# Ensemble_ProtoBoard.net
KiCad netlist of a schematic drawn in EAGLE
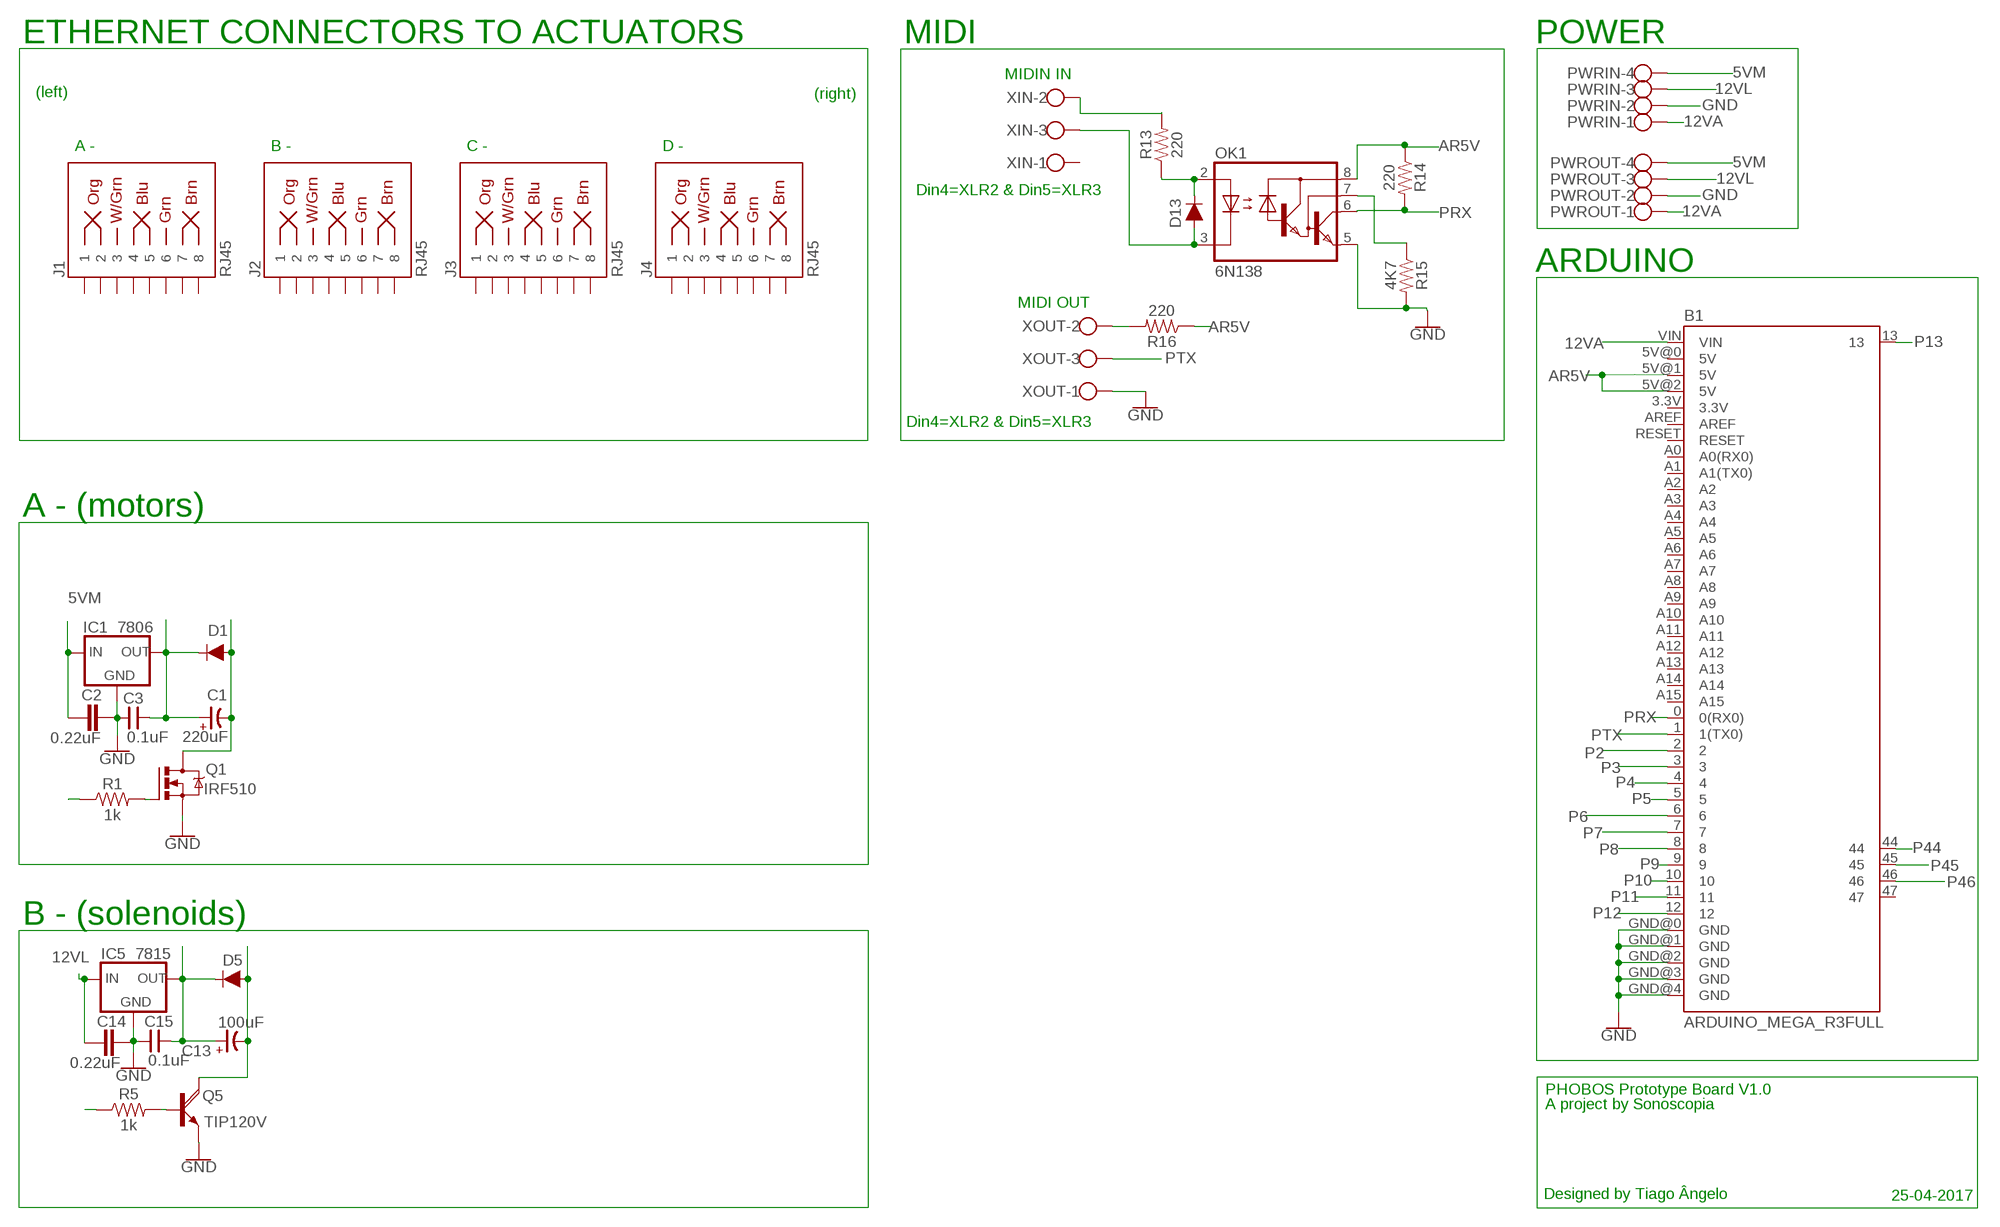
[diagram p0: schematic, sheet 1]

(export (version "E")
  (design (tool "Eeschema 10.0.6"))
  (components
    (comp (ref "B1")
      (value "ARDUINO_MEGA_R3FULL")
      (footprint "eagle-import:ARDUINO_MEGA")
      (libsource (lib "eagle-import") (part "ARDUINO_MEGA_R3FULL"))
    )
    (comp (ref "C1")
      (value "220uF")
      (footprint "eagle-import:E-035X080")
      (libsource (lib "eagle-import") (part "CP-E-035X080"))
    )
    (comp (ref "C2")
      (value "0.22uF")
      (footprint "eagle-import:C5B3")
      (libsource (lib "eagle-import") (part "C5/3"))
    )
    (comp (ref "C3")
      (value "0.1uF")
      (footprint "eagle-import:C025-050X025")
      (libsource (lib "eagle-import") (part "CNP-C025-050X025"))
    )
    (comp (ref "C13")
      (value "100uF")
      (footprint "eagle-import:E-020X050")
      (libsource (lib "eagle-import") (part "CP-E-020X050"))
    )
    (comp (ref "C14")
      (value "0.22uF")
      (footprint "eagle-import:C5B3")
      (libsource (lib "eagle-import") (part "C5/3"))
    )
    (comp (ref "C15")
      (value "0.1uF")
      (footprint "eagle-import:C025-050X025")
      (libsource (lib "eagle-import") (part "CNP-C025-050X025"))
    )
    (comp (ref "D1")
      (value "1A/50V/1.1V")
      (footprint "eagle-import:DIODE-1N4001-KIT")
      (libsource (lib "eagle-import") (part "DIODE-KIT2"))
    )
    (comp (ref "D5")
      (value "1A/50V/1.1V")
      (footprint "eagle-import:DIODE-1N4001-KIT")
      (libsource (lib "eagle-import") (part "DIODE-KIT2"))
    )
    (comp (ref "D13")
      (value "200mA/100V/1V")
      (footprint "eagle-import:DIODE-1N4148")
      (libsource (lib "eagle-import") (part "DIODE-1N4148"))
    )
    (comp (ref "IC1")
      (value "7806")
      (footprint "eagle-import:78XXS")
      (libsource (lib "eagle-import") (part "78XXS"))
    )
    (comp (ref "IC5")
      (value "7815")
      (footprint "eagle-import:78XXS")
      (libsource (lib "eagle-import") (part "78XXS"))
    )
    (comp (ref "J1")
      (value "RJ45")
      (footprint "eagle-import:RJ45-8")
      (libsource (lib "eagle-import") (part "RJ45-8"))
    )
    (comp (ref "J2")
      (value "RJ45")
      (footprint "eagle-import:RJ45-8")
      (libsource (lib "eagle-import") (part "RJ45-8"))
    )
    (comp (ref "J3")
      (value "RJ45")
      (footprint "eagle-import:RJ45-8")
      (libsource (lib "eagle-import") (part "RJ45-8"))
    )
    (comp (ref "J4")
      (value "RJ45")
      (footprint "eagle-import:RJ45-8")
      (libsource (lib "eagle-import") (part "RJ45-8"))
    )
    (comp (ref "OK1")
      (value "6N138")
      (footprint "eagle-import:DIL08")
      (fields (field (name "MF") "VISHAY/TELEFUNKEN"))
      (libsource (lib "eagle-import") (part "6N138"))
    )
    (comp (ref "PWRIN")
      (value "W237-4")
      (footprint "eagle-import:W237-4")
      (libsource (lib "eagle-import") (part "W237-4"))
    )
    (comp (ref "PWROUT")
      (value "W237-4")
      (footprint "eagle-import:W237-4")
      (libsource (lib "eagle-import") (part "W237-4"))
    )
    (comp (ref "Q1")
      (value "IRF510")
      (footprint "eagle-import:TO220BV")
      (libsource (lib "eagle-import") (part "IRF520"))
    )
    (comp (ref "Q5")
      (value "TIP120V")
      (footprint "eagle-import:TO220AV")
      (libsource (lib "eagle-import") (part "TIP120V"))
    )
    (comp (ref "R1")
      (value "1k")
      (footprint "eagle-import:AXIAL-0.1")
      (libsource (lib "eagle-import") (part "1KOHM-VERT-1/4W-1%"))
    )
    (comp (ref "R5")
      (value "1k")
      (footprint "eagle-import:AXIAL-0.1")
      (libsource (lib "eagle-import") (part "1KOHM-VERT-1/4W-1%"))
    )
    (comp (ref "R13")
      (value "220")
      (footprint "eagle-import:AXIAL-0.3")
      (libsource (lib "eagle-import") (part "1KOHM-HORIZ-1/4W-5%"))
    )
    (comp (ref "R14")
      (value "220")
      (footprint "eagle-import:AXIAL-0.3")
      (libsource (lib "eagle-import") (part "1KOHM-HORIZ-1/4W-5%"))
    )
    (comp (ref "R15")
      (value "4K7")
      (footprint "eagle-import:AXIAL-0.3")
      (libsource (lib "eagle-import") (part "1KOHM-HORIZ-1/4W-5%"))
    )
    (comp (ref "R16")
      (value "220")
      (footprint "eagle-import:AXIAL-0.3")
      (libsource (lib "eagle-import") (part "1KOHM-HORIZ-1/4W-5%"))
    )
    (comp (ref "XIN")
      (value "W237-103")
      (footprint "eagle-import:W237-103")
      (fields (field (name "MPN") "237-103"))
      (libsource (lib "eagle-import") (part "W237-103"))
    )
    (comp (ref "XOUT")
      (value "W237-103")
      (footprint "eagle-import:W237-103")
      (fields (field (name "MPN") "237-103"))
      (libsource (lib "eagle-import") (part "W237-103"))
    )
  )
  (nets
    (net (code "1") (name "/5VM") (class "Default")
      (node (ref "C2") (pin "1") (pinfunction "1_1") (pintype "passive"))
      (node (ref "IC1") (pin "IN") (pinfunction "IN_IN") (pintype "input"))
      (node (ref "PWRIN") (pin "4") (pinfunction "KL_4") (pintype "passive"))
      (node (ref "PWROUT") (pin "4") (pinfunction "KL_4") (pintype "passive"))
    )
    (net (code "2") (name "/12VA") (class "Default")
      (node (ref "B1") (pin "VIN") (pinfunction "VIN_VIN") (pintype "bidirectional"))
      (node (ref "PWRIN") (pin "1") (pinfunction "KL_1") (pintype "passive"))
      (node (ref "PWROUT") (pin "1") (pinfunction "KL_1") (pintype "passive"))
    )
    (net (code "3") (name "/12VL") (class "Default")
      (node (ref "C14") (pin "1") (pinfunction "1_1") (pintype "passive"))
      (node (ref "IC5") (pin "IN") (pinfunction "IN_IN") (pintype "input"))
      (node (ref "PWRIN") (pin "3") (pinfunction "KL_3") (pintype "passive"))
      (node (ref "PWROUT") (pin "3") (pinfunction "KL_3") (pintype "passive"))
    )
    (net (code "4") (name "/AR5V") (class "Default")
      (node (ref "B1") (pin "5V@1") (pinfunction "5V_5V@1") (pintype "bidirectional"))
      (node (ref "B1") (pin "5V@2") (pinfunction "5V_5V@2") (pintype "bidirectional"))
      (node (ref "OK1") (pin "8") (pinfunction "VCC_8") (pintype "passive"))
      (node (ref "R14") (pin "P$1") (pinfunction "1_P$1") (pintype "passive"))
      (node (ref "R16") (pin "P$1") (pinfunction "1_P$1") (pintype "passive"))
    )
    (net (code "5") (name "/N$1") (class "Default")
      (node (ref "C1") (pin "+") (pinfunction "+_+") (pintype "passive"))
      (node (ref "C3") (pin "2") (pinfunction "2_2") (pintype "passive"))
      (node (ref "D1") (pin "C") (pinfunction "C_C") (pintype "passive"))
      (node (ref "IC1") (pin "OUT") (pinfunction "OUT_OUT") (pintype "passive"))
      (node (ref "Q1") (pin "G") (pinfunction "G_G") (pintype "passive"))
      (node (ref "R1") (pin "P$2") (pinfunction "2_P$2") (pintype "passive"))
    )
    (net (code "6") (name "/N$2") (class "Default")
      (node (ref "C1") (pin "-") (pinfunction "-_-") (pintype "passive"))
      (node (ref "D1") (pin "A") (pinfunction "A_A") (pintype "passive"))
      (node (ref "Q1") (pin "D") (pinfunction "D_D") (pintype "passive"))
      (node (ref "R16") (pin "P$2") (pinfunction "2_P$2") (pintype "passive"))
      (node (ref "XOUT") (pin "2") (pinfunction "KL_2") (pintype "passive"))
    )
    (net (code "7") (name "/P2") (class "Default")
      (node (ref "B1") (pin "2") (pinfunction "2_2") (pintype "bidirectional"))
    )
    (net (code "8") (name "/P3") (class "Default")
      (node (ref "B1") (pin "3") (pinfunction "3_3") (pintype "bidirectional"))
    )
    (net (code "9") (name "/P4") (class "Default")
      (node (ref "B1") (pin "4") (pinfunction "4_4") (pintype "bidirectional"))
    )
    (net (code "10") (name "/P5") (class "Default")
      (node (ref "B1") (pin "5") (pinfunction "5_5") (pintype "bidirectional"))
    )
    (net (code "11") (name "/P6") (class "Default")
      (node (ref "B1") (pin "6") (pinfunction "6_6") (pintype "bidirectional"))
    )
    (net (code "12") (name "/P7") (class "Default")
      (node (ref "B1") (pin "7") (pinfunction "7_7") (pintype "bidirectional"))
    )
    (net (code "13") (name "/P8") (class "Default")
      (node (ref "B1") (pin "8") (pinfunction "8_8") (pintype "bidirectional"))
    )
    (net (code "14") (name "/P9") (class "Default")
      (node (ref "B1") (pin "9") (pinfunction "9_9") (pintype "bidirectional"))
    )
    (net (code "15") (name "/P10") (class "Default")
      (node (ref "B1") (pin "10") (pinfunction "10_10") (pintype "bidirectional"))
    )
    (net (code "16") (name "/P11") (class "Default")
      (node (ref "B1") (pin "11") (pinfunction "11_11") (pintype "bidirectional"))
    )
    (net (code "17") (name "/P12") (class "Default")
      (node (ref "B1") (pin "12") (pinfunction "12_12") (pintype "bidirectional"))
    )
    (net (code "18") (name "/P13") (class "Default")
      (node (ref "B1") (pin "13") (pinfunction "13_13") (pintype "bidirectional"))
    )
    (net (code "19") (name "/P44") (class "Default")
      (node (ref "B1") (pin "44") (pinfunction "44_44") (pintype "bidirectional"))
    )
    (net (code "20") (name "/P45") (class "Default")
      (node (ref "B1") (pin "45") (pinfunction "45_45") (pintype "bidirectional"))
    )
    (net (code "21") (name "/P46") (class "Default")
      (node (ref "B1") (pin "46") (pinfunction "46_46") (pintype "bidirectional"))
    )
    (net (code "22") (name "/PRX") (class "Default")
      (node (ref "B1") (pin "0") (pinfunction "0(RX0)_0") (pintype "bidirectional"))
      (node (ref "OK1") (pin "6") (pinfunction "VO_6") (pintype "passive"))
      (node (ref "R14") (pin "P$2") (pinfunction "2_P$2") (pintype "passive"))
    )
    (net (code "23") (name "/PTX") (class "Default")
      (node (ref "B1") (pin "1") (pinfunction "1(TX0)_1") (pintype "bidirectional"))
      (node (ref "XOUT") (pin "3") (pinfunction "KL_3") (pintype "passive"))
    )
    (net (code "24") (name "GND") (class "Default")
      (node (ref "B1") (pin "GND@0") (pinfunction "GND_GND@0") (pintype "bidirectional"))
      (node (ref "B1") (pin "GND@1") (pinfunction "GND_GND@1") (pintype "bidirectional"))
      (node (ref "B1") (pin "GND@2") (pinfunction "GND_GND@2") (pintype "bidirectional"))
      (node (ref "B1") (pin "GND@3") (pinfunction "GND_GND@3") (pintype "bidirectional"))
      (node (ref "B1") (pin "GND@4") (pinfunction "GND_GND@4") (pintype "bidirectional"))
      (node (ref "C14") (pin "2") (pinfunction "2_2") (pintype "passive"))
      (node (ref "C15") (pin "1") (pinfunction "1_1") (pintype "passive"))
      (node (ref "C2") (pin "2") (pinfunction "2_2") (pintype "passive"))
      (node (ref "C3") (pin "1") (pinfunction "1_1") (pintype "passive"))
      (node (ref "IC1") (pin "GND") (pinfunction "GND_GND") (pintype "input"))
      (node (ref "IC5") (pin "GND") (pinfunction "GND_GND") (pintype "input"))
      (node (ref "OK1") (pin "5") (pinfunction "GND_5") (pintype "passive"))
      (node (ref "PWRIN") (pin "2") (pinfunction "KL_2") (pintype "passive"))
      (node (ref "PWROUT") (pin "2") (pinfunction "KL_2") (pintype "passive"))
      (node (ref "Q1") (pin "S") (pinfunction "S_S") (pintype "passive"))
      (node (ref "Q5") (pin "E") (pinfunction "E_E") (pintype "passive"))
      (node (ref "R15") (pin "P$2") (pinfunction "2_P$2") (pintype "passive"))
      (node (ref "XOUT") (pin "1") (pinfunction "KL_1") (pintype "passive"))
    )
    (net (code "25") (name "Net-(C13-Pad+)") (class "Default")
      (node (ref "C13") (pin "+") (pinfunction "+_+") (pintype "passive"))
      (node (ref "C15") (pin "2") (pinfunction "2_2") (pintype "passive"))
      (node (ref "D5") (pin "C") (pinfunction "C_C") (pintype "passive"))
      (node (ref "IC5") (pin "OUT") (pinfunction "OUT_OUT") (pintype "passive"))
    )
    (net (code "26") (name "Net-(C13-Pad-)") (class "Default")
      (node (ref "C13") (pin "-") (pinfunction "-_-") (pintype "passive"))
      (node (ref "D5") (pin "A") (pinfunction "A_A") (pintype "passive"))
      (node (ref "Q5") (pin "C") (pinfunction "C_C") (pintype "passive"))
    )
    (net (code "27") (name "Net-(OK1-A)") (class "Default")
      (node (ref "D13") (pin "C") (pinfunction "C_C") (pintype "passive"))
      (node (ref "OK1") (pin "2") (pinfunction "A_2") (pintype "passive"))
      (node (ref "R13") (pin "P$1") (pinfunction "1_P$1") (pintype "passive"))
    )
    (net (code "28") (name "Net-(OK1-C)") (class "Default")
      (node (ref "D13") (pin "A") (pinfunction "A_A") (pintype "passive"))
      (node (ref "OK1") (pin "3") (pinfunction "C_3") (pintype "passive"))
      (node (ref "XIN") (pin "3") (pinfunction "KL_3") (pintype "passive"))
    )
    (net (code "29") (name "Net-(OK1-VB)") (class "Default")
      (node (ref "OK1") (pin "7") (pinfunction "VB_7") (pintype "passive"))
      (node (ref "R15") (pin "P$1") (pinfunction "1_P$1") (pintype "passive"))
    )
    (net (code "30") (name "Net-(R5-2)") (class "Default")
      (node (ref "Q5") (pin "B") (pinfunction "B_B") (pintype "passive"))
      (node (ref "R5") (pin "P$2") (pinfunction "2_P$2") (pintype "passive"))
    )
    (net (code "31") (name "Net-(R13-2)") (class "Default")
      (node (ref "R13") (pin "P$2") (pinfunction "2_P$2") (pintype "passive"))
      (node (ref "XIN") (pin "2") (pinfunction "KL_2") (pintype "passive"))
    )
    (net (code "32") (name "unconnected-(B1-5V-Pad5V@0)") (class "Default")
      (node (ref "B1") (pin "5V@0") (pinfunction "5V_5V@0") (pintype "bidirectional"))
    )
    (net (code "33") (name "unconnected-(B1-A0(RX0)-PadA0)") (class "Default")
      (node (ref "B1") (pin "A0") (pinfunction "A0(RX0)_A0") (pintype "bidirectional"))
    )
    (net (code "34") (name "unconnected-(B1-A1(TX0)-PadA1)") (class "Default")
      (node (ref "B1") (pin "A1") (pinfunction "A1(TX0)_A1") (pintype "bidirectional"))
    )
    (net (code "35") (name "unconnected-(B1-Pad3.3V)") (class "Default")
      (node (ref "B1") (pin "3.3V") (pinfunction "3.3V_3.3V") (pintype "bidirectional"))
    )
    (net (code "36") (name "unconnected-(B1-Pad47)") (class "Default")
      (node (ref "B1") (pin "47") (pinfunction "47_47") (pintype "bidirectional"))
    )
    (net (code "37") (name "unconnected-(B1-PadA2)") (class "Default")
      (node (ref "B1") (pin "A2") (pinfunction "A2_A2") (pintype "bidirectional"))
    )
    (net (code "38") (name "unconnected-(B1-PadA3)") (class "Default")
      (node (ref "B1") (pin "A3") (pinfunction "A3_A3") (pintype "bidirectional"))
    )
    (net (code "39") (name "unconnected-(B1-PadA4)") (class "Default")
      (node (ref "B1") (pin "A4") (pinfunction "A4_A4") (pintype "bidirectional"))
    )
    (net (code "40") (name "unconnected-(B1-PadA5)") (class "Default")
      (node (ref "B1") (pin "A5") (pinfunction "A5_A5") (pintype "bidirectional"))
    )
    (net (code "41") (name "unconnected-(B1-PadA6)") (class "Default")
      (node (ref "B1") (pin "A6") (pinfunction "A6_A6") (pintype "bidirectional"))
    )
    (net (code "42") (name "unconnected-(B1-PadA7)") (class "Default")
      (node (ref "B1") (pin "A7") (pinfunction "A7_A7") (pintype "bidirectional"))
    )
    (net (code "43") (name "unconnected-(B1-PadA8)") (class "Default")
      (node (ref "B1") (pin "A8") (pinfunction "A8_A8") (pintype "bidirectional"))
    )
    (net (code "44") (name "unconnected-(B1-PadA9)") (class "Default")
      (node (ref "B1") (pin "A9") (pinfunction "A9_A9") (pintype "bidirectional"))
    )
    (net (code "45") (name "unconnected-(B1-PadA10)") (class "Default")
      (node (ref "B1") (pin "A10") (pinfunction "A10_A10") (pintype "bidirectional"))
    )
    (net (code "46") (name "unconnected-(B1-PadA11)") (class "Default")
      (node (ref "B1") (pin "A11") (pinfunction "A11_A11") (pintype "bidirectional"))
    )
    (net (code "47") (name "unconnected-(B1-PadA12)") (class "Default")
      (node (ref "B1") (pin "A12") (pinfunction "A12_A12") (pintype "bidirectional"))
    )
    (net (code "48") (name "unconnected-(B1-PadA13)") (class "Default")
      (node (ref "B1") (pin "A13") (pinfunction "A13_A13") (pintype "bidirectional"))
    )
    (net (code "49") (name "unconnected-(B1-PadA14)") (class "Default")
      (node (ref "B1") (pin "A14") (pinfunction "A14_A14") (pintype "bidirectional"))
    )
    (net (code "50") (name "unconnected-(B1-PadA15)") (class "Default")
      (node (ref "B1") (pin "A15") (pinfunction "A15_A15") (pintype "bidirectional"))
    )
    (net (code "51") (name "unconnected-(B1-PadAREF)") (class "Default")
      (node (ref "B1") (pin "AREF") (pinfunction "AREF_AREF") (pintype "bidirectional"))
    )
    (net (code "52") (name "unconnected-(B1-PadRESET)") (class "Default")
      (node (ref "B1") (pin "RESET") (pinfunction "RESET_RESET") (pintype "bidirectional"))
    )
    (net (code "53") (name "unconnected-(J1-Pad1)") (class "Default")
      (node (ref "J1") (pin "1") (pinfunction "1_1") (pintype "bidirectional"))
    )
    (net (code "54") (name "unconnected-(J1-Pad2)") (class "Default")
      (node (ref "J1") (pin "2") (pinfunction "2_2") (pintype "bidirectional"))
    )
    (net (code "55") (name "unconnected-(J1-Pad3)") (class "Default")
      (node (ref "J1") (pin "3") (pinfunction "3_3") (pintype "bidirectional"))
    )
    (net (code "56") (name "unconnected-(J1-Pad4)") (class "Default")
      (node (ref "J1") (pin "4") (pinfunction "4_4") (pintype "bidirectional"))
    )
    (net (code "57") (name "unconnected-(J1-Pad5)") (class "Default")
      (node (ref "J1") (pin "5") (pinfunction "5_5") (pintype "bidirectional"))
    )
    (net (code "58") (name "unconnected-(J1-Pad6)") (class "Default")
      (node (ref "J1") (pin "6") (pinfunction "6_6") (pintype "bidirectional"))
    )
    (net (code "59") (name "unconnected-(J1-Pad7)") (class "Default")
      (node (ref "J1") (pin "7") (pinfunction "7_7") (pintype "bidirectional"))
    )
    (net (code "60") (name "unconnected-(J1-Pad8)") (class "Default")
      (node (ref "J1") (pin "8") (pinfunction "8_8") (pintype "bidirectional"))
    )
    (net (code "61") (name "unconnected-(J2-Pad1)") (class "Default")
      (node (ref "J2") (pin "1") (pinfunction "1_1") (pintype "bidirectional"))
    )
    (net (code "62") (name "unconnected-(J2-Pad2)") (class "Default")
      (node (ref "J2") (pin "2") (pinfunction "2_2") (pintype "bidirectional"))
    )
    (net (code "63") (name "unconnected-(J2-Pad3)") (class "Default")
      (node (ref "J2") (pin "3") (pinfunction "3_3") (pintype "bidirectional"))
    )
    (net (code "64") (name "unconnected-(J2-Pad4)") (class "Default")
      (node (ref "J2") (pin "4") (pinfunction "4_4") (pintype "bidirectional"))
    )
    (net (code "65") (name "unconnected-(J2-Pad5)") (class "Default")
      (node (ref "J2") (pin "5") (pinfunction "5_5") (pintype "bidirectional"))
    )
    (net (code "66") (name "unconnected-(J2-Pad6)") (class "Default")
      (node (ref "J2") (pin "6") (pinfunction "6_6") (pintype "bidirectional"))
    )
    (net (code "67") (name "unconnected-(J2-Pad7)") (class "Default")
      (node (ref "J2") (pin "7") (pinfunction "7_7") (pintype "bidirectional"))
    )
    (net (code "68") (name "unconnected-(J2-Pad8)") (class "Default")
      (node (ref "J2") (pin "8") (pinfunction "8_8") (pintype "bidirectional"))
    )
    (net (code "69") (name "unconnected-(J3-Pad1)") (class "Default")
      (node (ref "J3") (pin "1") (pinfunction "1_1") (pintype "bidirectional"))
    )
    (net (code "70") (name "unconnected-(J3-Pad2)") (class "Default")
      (node (ref "J3") (pin "2") (pinfunction "2_2") (pintype "bidirectional"))
    )
    (net (code "71") (name "unconnected-(J3-Pad3)") (class "Default")
      (node (ref "J3") (pin "3") (pinfunction "3_3") (pintype "bidirectional"))
    )
    (net (code "72") (name "unconnected-(J3-Pad4)") (class "Default")
      (node (ref "J3") (pin "4") (pinfunction "4_4") (pintype "bidirectional"))
    )
    (net (code "73") (name "unconnected-(J3-Pad5)") (class "Default")
      (node (ref "J3") (pin "5") (pinfunction "5_5") (pintype "bidirectional"))
    )
    (net (code "74") (name "unconnected-(J3-Pad6)") (class "Default")
      (node (ref "J3") (pin "6") (pinfunction "6_6") (pintype "bidirectional"))
    )
    (net (code "75") (name "unconnected-(J3-Pad7)") (class "Default")
      (node (ref "J3") (pin "7") (pinfunction "7_7") (pintype "bidirectional"))
    )
    (net (code "76") (name "unconnected-(J3-Pad8)") (class "Default")
      (node (ref "J3") (pin "8") (pinfunction "8_8") (pintype "bidirectional"))
    )
    (net (code "77") (name "unconnected-(J4-Pad1)") (class "Default")
      (node (ref "J4") (pin "1") (pinfunction "1_1") (pintype "bidirectional"))
    )
    (net (code "78") (name "unconnected-(J4-Pad2)") (class "Default")
      (node (ref "J4") (pin "2") (pinfunction "2_2") (pintype "bidirectional"))
    )
    (net (code "79") (name "unconnected-(J4-Pad3)") (class "Default")
      (node (ref "J4") (pin "3") (pinfunction "3_3") (pintype "bidirectional"))
    )
    (net (code "80") (name "unconnected-(J4-Pad4)") (class "Default")
      (node (ref "J4") (pin "4") (pinfunction "4_4") (pintype "bidirectional"))
    )
    (net (code "81") (name "unconnected-(J4-Pad5)") (class "Default")
      (node (ref "J4") (pin "5") (pinfunction "5_5") (pintype "bidirectional"))
    )
    (net (code "82") (name "unconnected-(J4-Pad6)") (class "Default")
      (node (ref "J4") (pin "6") (pinfunction "6_6") (pintype "bidirectional"))
    )
    (net (code "83") (name "unconnected-(J4-Pad7)") (class "Default")
      (node (ref "J4") (pin "7") (pinfunction "7_7") (pintype "bidirectional"))
    )
    (net (code "84") (name "unconnected-(J4-Pad8)") (class "Default")
      (node (ref "J4") (pin "8") (pinfunction "8_8") (pintype "bidirectional"))
    )
    (net (code "85") (name "unconnected-(R1-1-PadP$1)") (class "Default")
      (node (ref "R1") (pin "P$1") (pinfunction "1_P$1") (pintype "passive"))
    )
    (net (code "86") (name "unconnected-(R5-1-PadP$1)") (class "Default")
      (node (ref "R5") (pin "P$1") (pinfunction "1_P$1") (pintype "passive"))
    )
    (net (code "87") (name "unconnected-(XINA-KL-Pad1)") (class "Default")
      (node (ref "XIN") (pin "1") (pinfunction "KL_1") (pintype "passive"))
    )
  )
)
